# m3406.net
KiCad netlist of a schematic drawn in Altium Designer
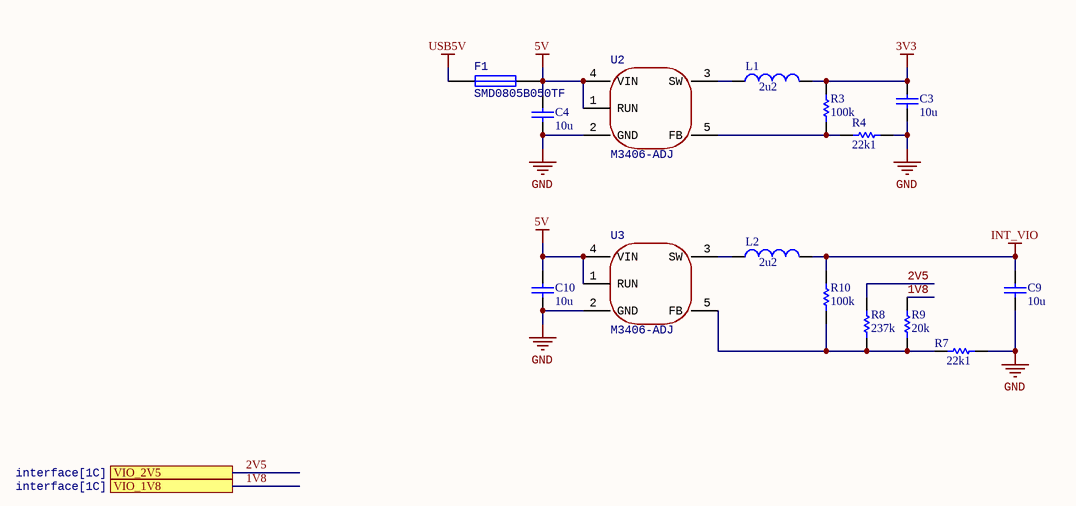
[diagram p0: m3406.SchDoc]

(export (version "E")
  (design (tool "Eeschema 10.0.6"))
  (components
    (comp (ref "C3")
      (value "10u")
      (footprint "CAPC160X80X90L30N")
      (fields
        (field (name "MPN") "TCC0603X5R106K100CT")
        (field (name "MANUFACTURER") "CCTC(三环)")
        (field (name "Comment") "Capacitor")
      )
      (libsource (lib "std_lib") (part "Capacitor"))
    )
    (comp (ref "C4")
      (value "10u")
      (footprint "CAPC160X80X90L30N")
      (fields
        (field (name "MPN") "TCC0603X5R106K100CT")
        (field (name "MANUFACTURER") "CCTC(三环)")
        (field (name "Comment") "Capacitor")
      )
      (libsource (lib "std_lib") (part "Capacitor"))
    )
    (comp (ref "C9")
      (value "10u")
      (footprint "CAPC160X80X90L30N")
      (fields
        (field (name "MPN") "TCC0603X5R106K100CT")
        (field (name "MANUFACTURER") "CCTC(三环)")
        (field (name "Comment") "Capacitor")
      )
      (libsource (lib "std_lib") (part "Capacitor"))
    )
    (comp (ref "C10")
      (value "10u")
      (footprint "CAPC160X80X90L30N")
      (fields
        (field (name "MPN") "TCC0603X5R106K100CT")
        (field (name "MANUFACTURER") "CCTC(三环)")
        (field (name "Comment") "Capacitor")
      )
      (libsource (lib "std_lib") (part "Capacitor"))
    )
    (comp (ref "F1")
      (value "SMD0805B050TF")
      (footprint "footprints:FUSC210X135X125L37N")
      (description "Fuse")
      (libsource (lib "Miscellaneous Devices") (part "Fuse 1"))
    )
    (comp (ref "L1")
      (value "2u2")
      (footprint "INDC200X160X105L60N")
      (fields
        (field (name "MPN") "SFE201610-2R2M")
        (field (name "MANUFACTURER") "DDY(德立)")
        (field (name "Comment") "Inductor")
      )
      (libsource (lib "std_lib") (part "Inductor"))
    )
    (comp (ref "L2")
      (value "2u2")
      (footprint "INDC200X160X105L60N")
      (fields
        (field (name "MPN") "SFE201610-2R2M")
        (field (name "MANUFACTURER") "DDY(德立)")
        (field (name "Comment") "Inductor")
      )
      (libsource (lib "std_lib") (part "Inductor"))
    )
    (comp (ref "R3")
      (value "100k")
      (footprint "RESC100X50X35L25N")
      (fields
        (field (name "MPN") "RTT021003FTH")
        (field (name "MANUFACTURER") "RALEC(旺诠)")
        (field (name "Comment") "Resistor")
      )
      (libsource (lib "std_lib") (part "Resistor"))
    )
    (comp (ref "R4")
      (value "22k1")
      (footprint "RESC100X50X35L25N")
      (fields
        (field (name "MPN") "RTT022212FTH")
        (field (name "MANUFACTURER") "RALEC(旺诠)")
        (field (name "Comment") "Resistor")
      )
      (libsource (lib "std_lib") (part "Resistor"))
    )
    (comp (ref "R7")
      (value "22k1")
      (footprint "RESC100X50X35L25N")
      (fields
        (field (name "MPN") "RTT022212FTH")
        (field (name "MANUFACTURER") "RALEC(旺诠)")
        (field (name "Comment") "Resistor")
      )
      (libsource (lib "std_lib") (part "Resistor"))
    )
    (comp (ref "R8")
      (value "237k")
      (footprint "RESC100X50X35L25N")
      (fields
        (field (name "MPN") "0402WGF2373TCE")
        (field (name "MANUFACTURER") "UNI-ROYAL(厚声)")
        (field (name "Comment") "Resistor")
      )
      (libsource (lib "std_lib") (part "Resistor"))
    )
    (comp (ref "R9")
      (value "20k")
      (footprint "RESC100X50X35L25N")
      (fields
        (field (name "MPN") "RC-02W8062FT")
        (field (name "MANUFACTURER") "FH(风华)")
        (field (name "Comment") "80.6k")
      )
      (libsource (lib "std_lib") (part "Resistor"))
    )
    (comp (ref "R10")
      (value "100k")
      (footprint "RESC100X50X35L25N")
      (fields
        (field (name "MPN") "RTT021003FTH")
        (field (name "MANUFACTURER") "RALEC(旺诠)")
        (field (name "Comment") "Resistor")
      )
      (libsource (lib "std_lib") (part "Resistor"))
    )
    (comp (ref "U2")
      (value "M3406-ADJ")
      (footprint "SOT23-5P95_280X110L37X40N")
      (description "Vin=2V~6V,800mA,DCDC")
      (fields (field (name "MANUFACTURER") "西安航天民芯"))
      (libsource (lib "Sch") (part "M3406-ADJ"))
    )
    (comp (ref "U3")
      (value "M3406-ADJ")
      (footprint "SOT23-5P95_280X110L37X40N")
      (description "Vin=2V~6V,800mA,DCDC")
      (fields (field (name "MANUFACTURER") "西安航天民芯"))
      (libsource (lib "Sch") (part "M3406-ADJ"))
    )
  )
  (nets
    (net (code "1") (name "/1V8") (class "Default")
      (node (ref "R9") (pin "2") (pinfunction "2_2") (pintype "passive"))
    )
    (net (code "2") (name "/2V5") (class "Default")
      (node (ref "R8") (pin "2") (pinfunction "2_2") (pintype "passive"))
    )
    (net (code "3") (name "3V3") (class "Default")
      (node (ref "C3") (pin "2") (pinfunction "2_2") (pintype "passive"))
      (node (ref "L1") (pin "2") (pinfunction "2_2") (pintype "passive"))
      (node (ref "R3") (pin "2") (pinfunction "2_2") (pintype "passive"))
    )
    (net (code "4") (name "5V") (class "Default")
      (node (ref "C10") (pin "2") (pinfunction "2_2") (pintype "passive"))
      (node (ref "C4") (pin "2") (pinfunction "2_2") (pintype "passive"))
      (node (ref "F1") (pin "2") (pinfunction "2_2") (pintype "passive"))
      (node (ref "U2") (pin "1") (pinfunction "RUN_1") (pintype "passive"))
      (node (ref "U2") (pin "4") (pinfunction "VIN_4") (pintype "passive"))
      (node (ref "U3") (pin "1") (pinfunction "RUN_1") (pintype "passive"))
      (node (ref "U3") (pin "4") (pinfunction "VIN_4") (pintype "passive"))
    )
    (net (code "5") (name "GND") (class "Default")
      (node (ref "C10") (pin "1") (pinfunction "1_1") (pintype "passive"))
      (node (ref "C3") (pin "1") (pinfunction "1_1") (pintype "passive"))
      (node (ref "C4") (pin "1") (pinfunction "1_1") (pintype "passive"))
      (node (ref "C9") (pin "1") (pinfunction "1_1") (pintype "passive"))
      (node (ref "R4") (pin "1") (pinfunction "1_1") (pintype "passive"))
      (node (ref "R7") (pin "1") (pinfunction "1_1") (pintype "passive"))
      (node (ref "U2") (pin "2") (pinfunction "GND_2") (pintype "passive"))
      (node (ref "U3") (pin "2") (pinfunction "GND_2") (pintype "passive"))
    )
    (net (code "6") (name "INT_VIO") (class "Default")
      (node (ref "C9") (pin "2") (pinfunction "2_2") (pintype "passive"))
      (node (ref "L2") (pin "2") (pinfunction "2_2") (pintype "passive"))
      (node (ref "R10") (pin "2") (pinfunction "2_2") (pintype "passive"))
    )
    (net (code "7") (name "Net-(U2-FB)") (class "Default")
      (node (ref "R3") (pin "1") (pinfunction "1_1") (pintype "passive"))
      (node (ref "R4") (pin "2") (pinfunction "2_2") (pintype "passive"))
      (node (ref "U2") (pin "5") (pinfunction "FB_5") (pintype "passive"))
    )
    (net (code "8") (name "Net-(U2-SW)") (class "Default")
      (node (ref "L1") (pin "1") (pinfunction "1_1") (pintype "passive"))
      (node (ref "U2") (pin "3") (pinfunction "SW_3") (pintype "passive"))
    )
    (net (code "9") (name "Net-(U3-FB)") (class "Default")
      (node (ref "R10") (pin "1") (pinfunction "1_1") (pintype "passive"))
      (node (ref "R7") (pin "2") (pinfunction "2_2") (pintype "passive"))
      (node (ref "R8") (pin "1") (pinfunction "1_1") (pintype "passive"))
      (node (ref "R9") (pin "1") (pinfunction "1_1") (pintype "passive"))
      (node (ref "U3") (pin "5") (pinfunction "FB_5") (pintype "passive"))
    )
    (net (code "10") (name "Net-(U3-SW)") (class "Default")
      (node (ref "L2") (pin "1") (pinfunction "1_1") (pintype "passive"))
      (node (ref "U3") (pin "3") (pinfunction "SW_3") (pintype "passive"))
    )
    (net (code "11") (name "USB5V") (class "Default")
      (node (ref "F1") (pin "1") (pinfunction "1_1") (pintype "passive"))
    )
  )
)
